# sensors.net
KiCad netlist of a schematic drawn in Altium Designer
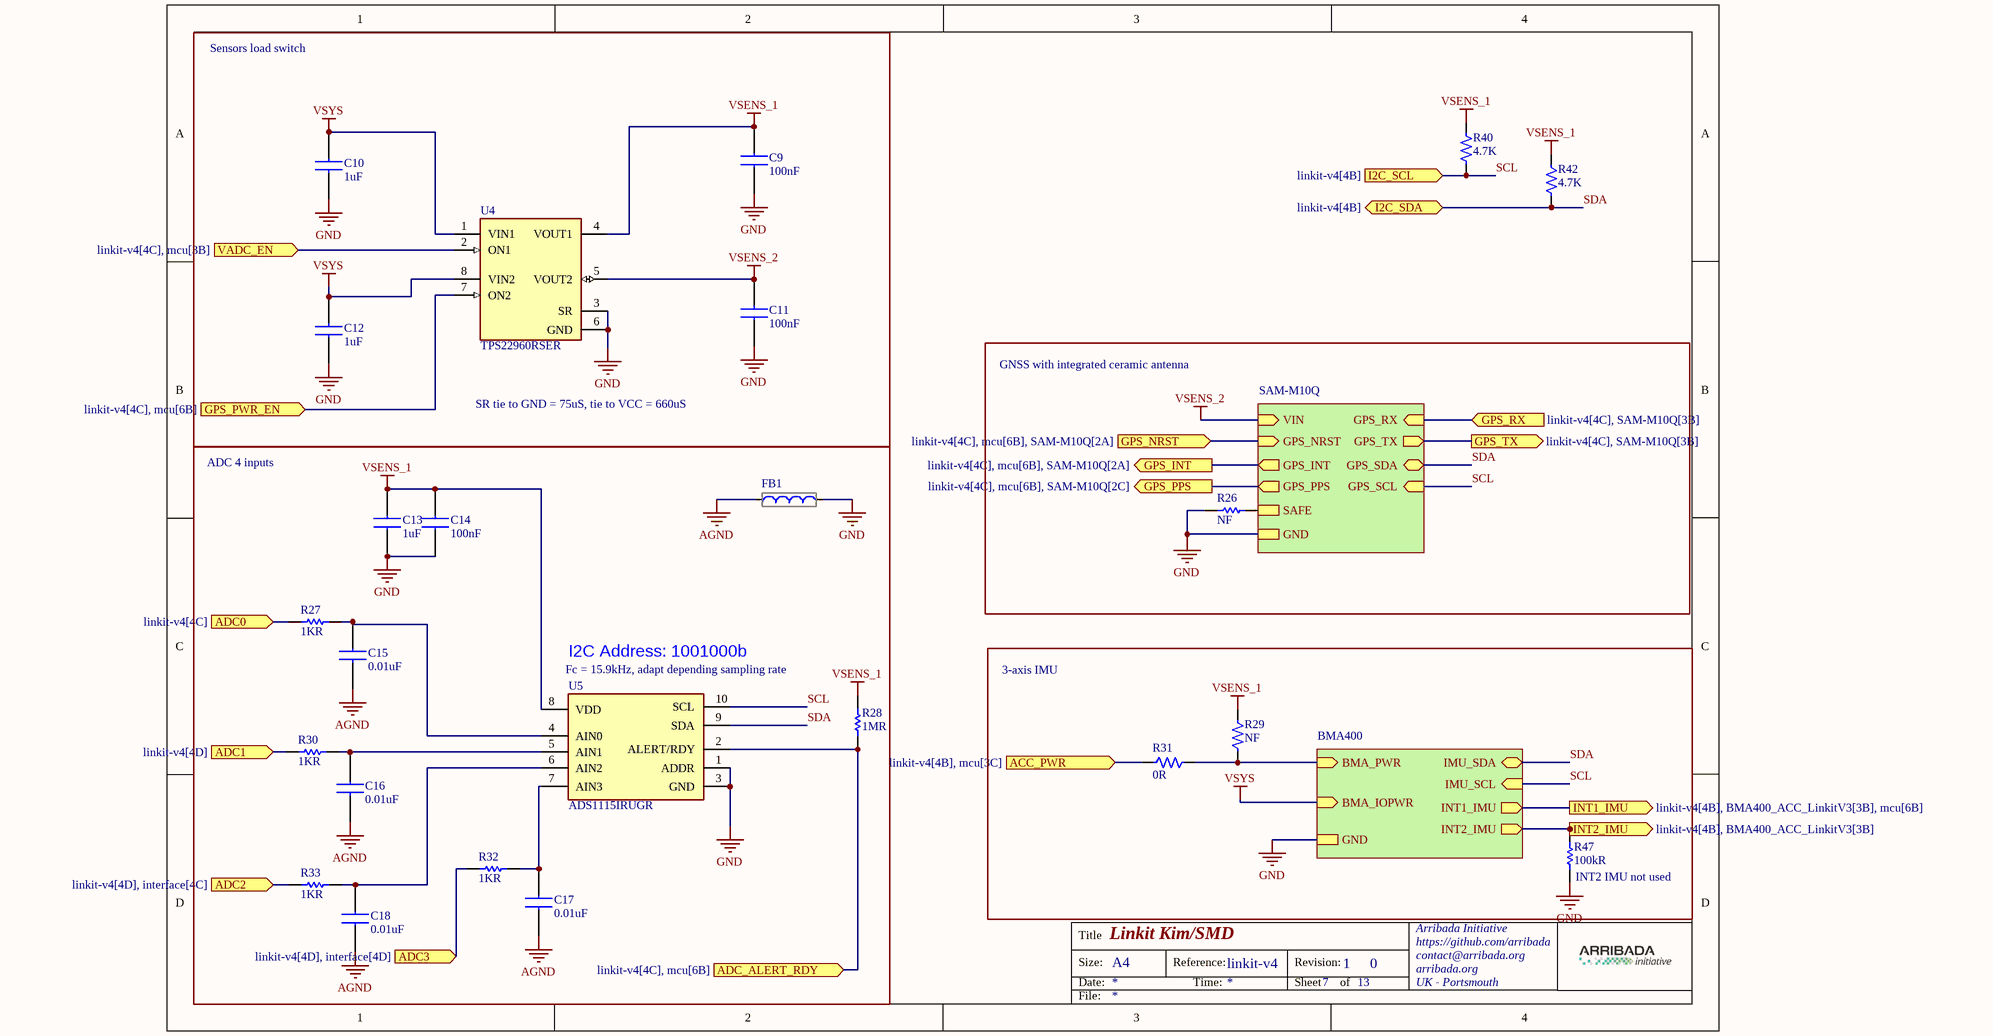
[diagram p0: sensors.SchDoc]

(export (version "E")
  (design (tool "Eeschema 10.0.6"))
  (components
    (comp (ref "C9")
      (value "100nF")
      (footprint "0402")
      (description "Multilayer Ceramic Capacitors MLCC - SMD/SMT 0.1 uF 16 VDC 10% 0402 X7R")
      (fields
        (field (name "MANUFACTURER_PART_NUMBER") "CC0402KRX7R7BB104")
        (field (name "MANUFACTURER") "YAGEO")
      )
      (libsource (lib "stm32wl-dev") (part "GRM155R71C104KA88D"))
    )
    (comp (ref "C10")
      (value "1uF")
      (footprint "CAPC1005X55N")
      (description "Multilayer Ceramic Capacitors MLCC - SMD/SMT 1.0UF 10V 10% 0402")
      (fields
        (field (name "MANUFACTURER_PART_NUMBER") "GRM155Z71A105KE01J")
        (field (name "MOUSER PART NUMBER") "81-GRM155Z71A105KE1J")
      )
      (libsource (lib "stm32wl-dev") (part "GRM155Z71A105KE01J"))
    )
    (comp (ref "C11")
      (value "100nF")
      (footprint "0402")
      (description "Multilayer Ceramic Capacitors MLCC - SMD/SMT 0.1 uF 16 VDC 10% 0402 X7R")
      (fields
        (field (name "MANUFACTURER_PART_NUMBER") "CC0402KRX7R7BB104")
        (field (name "MANUFACTURER") "YAGEO")
      )
      (libsource (lib "stm32wl-dev") (part "GRM155R71C104KA88D"))
    )
    (comp (ref "C12")
      (value "1uF")
      (footprint "CAPC1005X55N")
      (description "Multilayer Ceramic Capacitors MLCC - SMD/SMT 1.0UF 10V 10% 0402")
      (fields
        (field (name "MANUFACTURER_PART_NUMBER") "GRM155Z71A105KE01J")
        (field (name "MOUSER PART NUMBER") "81-GRM155Z71A105KE1J")
      )
      (libsource (lib "stm32wl-dev") (part "GRM155Z71A105KE01J"))
    )
    (comp (ref "C13")
      (value "1uF")
      (footprint "CAPC1005X55N")
      (description "Multilayer Ceramic Capacitors MLCC - SMD/SMT 1.0UF 10V 10% 0402")
      (fields
        (field (name "MANUFACTURER_PART_NUMBER") "GRM155Z71A105KE01J")
        (field (name "MOUSER PART NUMBER") "81-GRM155Z71A105KE1J")
      )
      (libsource (lib "stm32wl-dev") (part "GRM155Z71A105KE01J"))
    )
    (comp (ref "C14")
      (value "100nF")
      (footprint "0402")
      (description "Multilayer Ceramic Capacitors MLCC - SMD/SMT 0.1 uF 16 VDC 10% 0402 X7R")
      (fields
        (field (name "MANUFACTURER_PART_NUMBER") "CC0402KRX7R7BB104")
        (field (name "MANUFACTURER") "YAGEO")
      )
      (libsource (lib "stm32wl-dev") (part "GRM155R71C104KA88D"))
    )
    (comp (ref "C15")
      (value "0.01uF")
      (footprint "stm32wl-dev:GRM15x")
      (description "Multilayer Ceramic Capacitors MLCC - SMD/SMT 0.01 uF 35 VDC 2% 0402 C0G (NP0)")
      (fields
        (field (name "MANUFACTURER_PART_NUMBER") "GRM1555CYA103GE01D")
        (field (name "MOUSER PART NUMBER") "81-GRM1555CYA103GE1D")
      )
      (libsource (lib "stm32wl-dev") (part "GRM1555CYA103GE01D"))
    )
    (comp (ref "C16")
      (value "0.01uF")
      (footprint "stm32wl-dev:GRM15x")
      (description "Multilayer Ceramic Capacitors MLCC - SMD/SMT 0.01 uF 35 VDC 2% 0402 C0G (NP0)")
      (fields
        (field (name "MANUFACTURER_PART_NUMBER") "GRM1555CYA103GE01D")
        (field (name "MOUSER PART NUMBER") "81-GRM1555CYA103GE1D")
      )
      (libsource (lib "stm32wl-dev") (part "GRM1555CYA103GE01D"))
    )
    (comp (ref "C17")
      (value "0.01uF")
      (footprint "stm32wl-dev:GRM15x")
      (description "Multilayer Ceramic Capacitors MLCC - SMD/SMT 0.01 uF 35 VDC 2% 0402 C0G (NP0)")
      (fields
        (field (name "MANUFACTURER_PART_NUMBER") "GRM1555CYA103GE01D")
        (field (name "MOUSER PART NUMBER") "81-GRM1555CYA103GE1D")
      )
      (libsource (lib "stm32wl-dev") (part "GRM1555CYA103GE01D"))
    )
    (comp (ref "C18")
      (value "0.01uF")
      (footprint "stm32wl-dev:GRM15x")
      (description "Multilayer Ceramic Capacitors MLCC - SMD/SMT 0.01 uF 35 VDC 2% 0402 C0G (NP0)")
      (fields
        (field (name "MANUFACTURER_PART_NUMBER") "GRM1555CYA103GE01D")
        (field (name "MOUSER PART NUMBER") "81-GRM1555CYA103GE1D")
      )
      (libsource (lib "stm32wl-dev") (part "GRM1555CYA103GE01D"))
    )
    (comp (ref "FB1")
      (value "BLM18HE601SN1D")
      (footprint "stm32wl-dev:BLM18SP221SN1B")
      (description "Ferrite Beads 600 OHM 25%")
      (fields (field (name "MOUSER PART NUMBER") "81-BLM18HE601SN1D"))
      (libsource (lib "stm32wl-dev") (part "BLM18HE601SN1D"))
    )
    (comp (ref "R26")
      (value "NF")
      (footprint "R0402")
      (description "Generic Resistor, Not Fitted")
      (fields
        (field (name "INTERNAL_PART_NUMBER") "MCD-00052")
        (field (name "MANUFACTURER_PART_NUMBER") "RC0402JR-070RL")
        (field (name "PROVIDED_BY") "SUBCO")
      )
      (libsource (lib "stm32wl-dev") (part "RES-NC-0402"))
    )
    (comp (ref "R27")
      (value "1KR")
      (footprint "RESC0603X28N")
      (description "Thick Film Resistors - SMD 1/20watt 1Kohms 1% 200ppm")
      (fields
        (field (name "MANUFACTURER_PART_NUMBER") "CRCW02011K00FNED")
        (field (name "MOUSER PART NUMBER") "71-CRCW02011K00FNED")
      )
      (libsource (lib "stm32wl-dev") (part "CRCW02011K00FNED"))
    )
    (comp (ref "R28")
      (value "1MR")
      (footprint "RESC0603X26N")
      (description "Thick Film Resistors - SMD 1 MOhms 50 mW 0201 1%")
      (fields
        (field (name "MANUFACTURER_PART_NUMBER") "RC0201FR-7D1ML")
        (field (name "MOUSER PART NUMBER") "603-RC0201FR-7D1ML")
      )
      (libsource (lib "stm32wl-dev") (part "RC0201FR-7D1ML"))
    )
    (comp (ref "R29")
      (value "NF")
      (footprint "RES0402N_NF")
      (description "RES NF 0402")
      (fields (field (name "MANUFACTURER") "NOT FITTED PART"))
      (libsource (lib "Resistors") (part "RES NF 0402"))
    )
    (comp (ref "R30")
      (value "1KR")
      (footprint "RESC0603X28N")
      (description "Thick Film Resistors - SMD 1/20watt 1Kohms 1% 200ppm")
      (fields
        (field (name "MANUFACTURER_PART_NUMBER") "CRCW02011K00FNED")
        (field (name "MOUSER PART NUMBER") "71-CRCW02011K00FNED")
      )
      (libsource (lib "stm32wl-dev") (part "CRCW02011K00FNED"))
    )
    (comp (ref "R31")
      (value "0R")
      (footprint "RES0402N")
      (description "RES 0R 0402")
      (fields (field (name "Comment") "0R 0402"))
      (libsource (lib "Resistors") (part "RES 0R 0402"))
    )
    (comp (ref "R32")
      (value "1KR")
      (footprint "RESC0603X28N")
      (description "Thick Film Resistors - SMD 1/20watt 1Kohms 1% 200ppm")
      (fields
        (field (name "MANUFACTURER_PART_NUMBER") "CRCW02011K00FNED")
        (field (name "MOUSER PART NUMBER") "71-CRCW02011K00FNED")
      )
      (libsource (lib "stm32wl-dev") (part "CRCW02011K00FNED"))
    )
    (comp (ref "R33")
      (value "1KR")
      (footprint "RESC0603X28N")
      (description "Thick Film Resistors - SMD 1/20watt 1Kohms 1% 200ppm")
      (fields
        (field (name "MANUFACTURER_PART_NUMBER") "CRCW02011K00FNED")
        (field (name "MOUSER PART NUMBER") "71-CRCW02011K00FNED")
      )
      (libsource (lib "stm32wl-dev") (part "CRCW02011K00FNED"))
    )
    (comp (ref "R40")
      (value "4.7K")
      (footprint "RES0201L")
      (description "RES 4.7K 0201 1% 100PPM")
      (fields (field (name "TOLERANCE") "1%") (field (name "Comment") "4.7K 0201 1% 100PPM"))
      (libsource (lib "Resistors") (part "RES 4.7K 0201 1% 100PPM"))
    )
    (comp (ref "R42")
      (value "4.7K")
      (footprint "RES0201L")
      (description "RES 4.7K 0201 1% 100PPM")
      (fields (field (name "TOLERANCE") "1%") (field (name "Comment") "4.7K 0201 1% 100PPM"))
      (libsource (lib "Resistors") (part "RES 4.7K 0201 1% 100PPM"))
    )
    (comp (ref "R47")
      (value "100kR")
      (footprint "stm32wl-dev:RESC0603X28N")
      (description "Thick Film Resistors - SMD 1/20watt 100Kohms 5% 200ppm")
      (fields
        (field (name "MANUFACTURER_PART_NUMBER") "CRCW0201100KJNED")
        (field (name "MOUSER PART NUMBER") "71-CRCW0201100KJNED")
      )
      (libsource (lib "stm32wl-dev") (part "CRCW0201100KJNED"))
    )
    (comp (ref "U4")
      (value "TPS22960RSER")
      (footprint "stm32wl-dev:TPS22960RSER")
      (description "Power Switch ICs - Power Distribution Low Input VTG Dual L oad Switch")
      (fields (field (name "MOUSER PART NUMBER") "595-TPS22960RSER"))
      (libsource (lib "stm32wl-dev") (part "TPS22960RSER"))
    )
    (comp (ref "U5")
      (value "ADS1115IRUGR")
      (footprint "stm32wl-dev:ADS1115IRUGR")
      (description "Analog to Digital Converters - ADC 16B ADC w/ Int MUX P GA Comp Osc & Ref A")
      (fields (field (name "MOUSER PART NUMBER") "595-ADS1115IRUGR"))
      (libsource (lib "stm32wl-dev") (part "ADS1115IRUGR"))
    )
  )
  (nets
    (net (code "1") (name "/ACC_PWR") (class "Default")
      (node (ref "R31") (pin "1") (pinfunction "1_1") (pintype "passive"))
    )
    (net (code "2") (name "/ADC0") (class "Default")
      (node (ref "R27") (pin "1") (pinfunction "1_1") (pintype "passive"))
    )
    (net (code "3") (name "/ADC1") (class "Default")
      (node (ref "R30") (pin "1") (pinfunction "1_1") (pintype "passive"))
    )
    (net (code "4") (name "/ADC2") (class "Default")
      (node (ref "R33") (pin "1") (pinfunction "1_1") (pintype "passive"))
    )
    (net (code "5") (name "/ADC3") (class "Default")
      (node (ref "R32") (pin "1") (pinfunction "1_1") (pintype "passive"))
    )
    (net (code "6") (name "/ADC_ALERT_RDY") (class "Default")
      (node (ref "R28") (pin "2") (pinfunction "2_2") (pintype "passive"))
      (node (ref "U5") (pin "2") (pinfunction "ALERT/RDY_2") (pintype "passive"))
    )
    (net (code "7") (name "/BMA_PWR") (class "Default")
      (node (ref "R29") (pin "1") (pinfunction "1_1") (pintype "passive"))
      (node (ref "R31") (pin "2") (pinfunction "2_2") (pintype "passive"))
    )
    (net (code "11") (name "/GPS_PWR_EN") (class "Default")
      (node (ref "U4") (pin "7") (pinfunction "ON2_7") (pintype "input"))
    )
    (net (code "15") (name "/INT2_IMU") (class "Default")
      (node (ref "R47") (pin "1") (pinfunction "1_1") (pintype "passive"))
    )
    (net (code "16") (name "/SAFE") (class "Default")
      (node (ref "R26") (pin "2") (pinfunction "2_2") (pintype "passive"))
    )
    (net (code "17") (name "/SCL") (class "Default")
      (node (ref "R40") (pin "1") (pinfunction "1_1") (pintype "passive"))
      (node (ref "U5") (pin "10") (pinfunction "SCL_10") (pintype "passive"))
    )
    (net (code "18") (name "/SDA") (class "Default")
      (node (ref "R42") (pin "1") (pinfunction "1_1") (pintype "passive"))
      (node (ref "U5") (pin "9") (pinfunction "SDA_9") (pintype "passive"))
    )
    (net (code "19") (name "/VADC_EN") (class "Default")
      (node (ref "U4") (pin "2") (pinfunction "ON1_2") (pintype "input"))
    )
    (net (code "20") (name "AGND") (class "Default")
      (node (ref "C15") (pin "2") (pinfunction "2_2") (pintype "passive"))
      (node (ref "C16") (pin "2") (pinfunction "2_2") (pintype "passive"))
      (node (ref "C17") (pin "2") (pinfunction "2_2") (pintype "passive"))
      (node (ref "C18") (pin "2") (pinfunction "2_2") (pintype "passive"))
      (node (ref "FB1") (pin "1") (pinfunction "1_1") (pintype "passive"))
    )
    (net (code "21") (name "GND") (class "Default")
      (node (ref "C10") (pin "1") (pinfunction "1_1") (pintype "passive"))
      (node (ref "C11") (pin "2") (pinfunction "2_2") (pintype "passive"))
      (node (ref "C12") (pin "1") (pinfunction "1_1") (pintype "passive"))
      (node (ref "C13") (pin "1") (pinfunction "1_1") (pintype "passive"))
      (node (ref "C14") (pin "2") (pinfunction "2_2") (pintype "passive"))
      (node (ref "C9") (pin "2") (pinfunction "2_2") (pintype "passive"))
      (node (ref "FB1") (pin "2") (pinfunction "2_2") (pintype "passive"))
      (node (ref "R26") (pin "1") (pinfunction "1_1") (pintype "passive"))
      (node (ref "R47") (pin "2") (pinfunction "2_2") (pintype "passive"))
      (node (ref "U4") (pin "3") (pinfunction "SR_3") (pintype "power_in"))
      (node (ref "U4") (pin "6") (pinfunction "GND_6") (pintype "power_in"))
      (node (ref "U5") (pin "1") (pinfunction "ADDR_1") (pintype "passive"))
      (node (ref "U5") (pin "3") (pinfunction "GND_3") (pintype "passive"))
    )
    (net (code "22") (name "Net-(U5-AIN0)") (class "Default")
      (node (ref "C15") (pin "1") (pinfunction "1_1") (pintype "passive"))
      (node (ref "R27") (pin "2") (pinfunction "2_2") (pintype "passive"))
      (node (ref "U5") (pin "4") (pinfunction "AIN0_4") (pintype "passive"))
    )
    (net (code "23") (name "Net-(U5-AIN1)") (class "Default")
      (node (ref "C16") (pin "1") (pinfunction "1_1") (pintype "passive"))
      (node (ref "R30") (pin "2") (pinfunction "2_2") (pintype "passive"))
      (node (ref "U5") (pin "5") (pinfunction "AIN1_5") (pintype "passive"))
    )
    (net (code "24") (name "Net-(U5-AIN2)") (class "Default")
      (node (ref "C18") (pin "1") (pinfunction "1_1") (pintype "passive"))
      (node (ref "R33") (pin "2") (pinfunction "2_2") (pintype "passive"))
      (node (ref "U5") (pin "6") (pinfunction "AIN2_6") (pintype "passive"))
    )
    (net (code "25") (name "Net-(U5-AIN3)") (class "Default")
      (node (ref "C17") (pin "1") (pinfunction "1_1") (pintype "passive"))
      (node (ref "R32") (pin "2") (pinfunction "2_2") (pintype "passive"))
      (node (ref "U5") (pin "7") (pinfunction "AIN3_7") (pintype "passive"))
    )
    (net (code "26") (name "VSENS_1") (class "Default")
      (node (ref "C13") (pin "2") (pinfunction "2_2") (pintype "passive"))
      (node (ref "C14") (pin "1") (pinfunction "1_1") (pintype "passive"))
      (node (ref "C9") (pin "1") (pinfunction "1_1") (pintype "passive"))
      (node (ref "R28") (pin "1") (pinfunction "1_1") (pintype "passive"))
      (node (ref "R29") (pin "2") (pinfunction "2_2") (pintype "passive"))
      (node (ref "R40") (pin "2") (pinfunction "2_2") (pintype "passive"))
      (node (ref "R42") (pin "2") (pinfunction "2_2") (pintype "passive"))
      (node (ref "U4") (pin "4") (pinfunction "VOUT1_4") (pintype "power_in"))
      (node (ref "U5") (pin "8") (pinfunction "VDD_8") (pintype "passive"))
    )
    (net (code "27") (name "VSENS_2") (class "Default")
      (node (ref "C11") (pin "1") (pinfunction "1_1") (pintype "passive"))
      (node (ref "U4") (pin "5") (pinfunction "VOUT2_5") (pintype "bidirectional"))
    )
    (net (code "28") (name "VSYS") (class "Default")
      (node (ref "C10") (pin "2") (pinfunction "2_2") (pintype "passive"))
      (node (ref "C12") (pin "2") (pinfunction "2_2") (pintype "passive"))
      (node (ref "U4") (pin "1") (pinfunction "VIN1_1") (pintype "power_in"))
      (node (ref "U4") (pin "8") (pinfunction "VIN2_8") (pintype "power_in"))
    )
  )
)
